# Mother_board1.net
KiCad netlist of a schematic drawn in Altium Designer
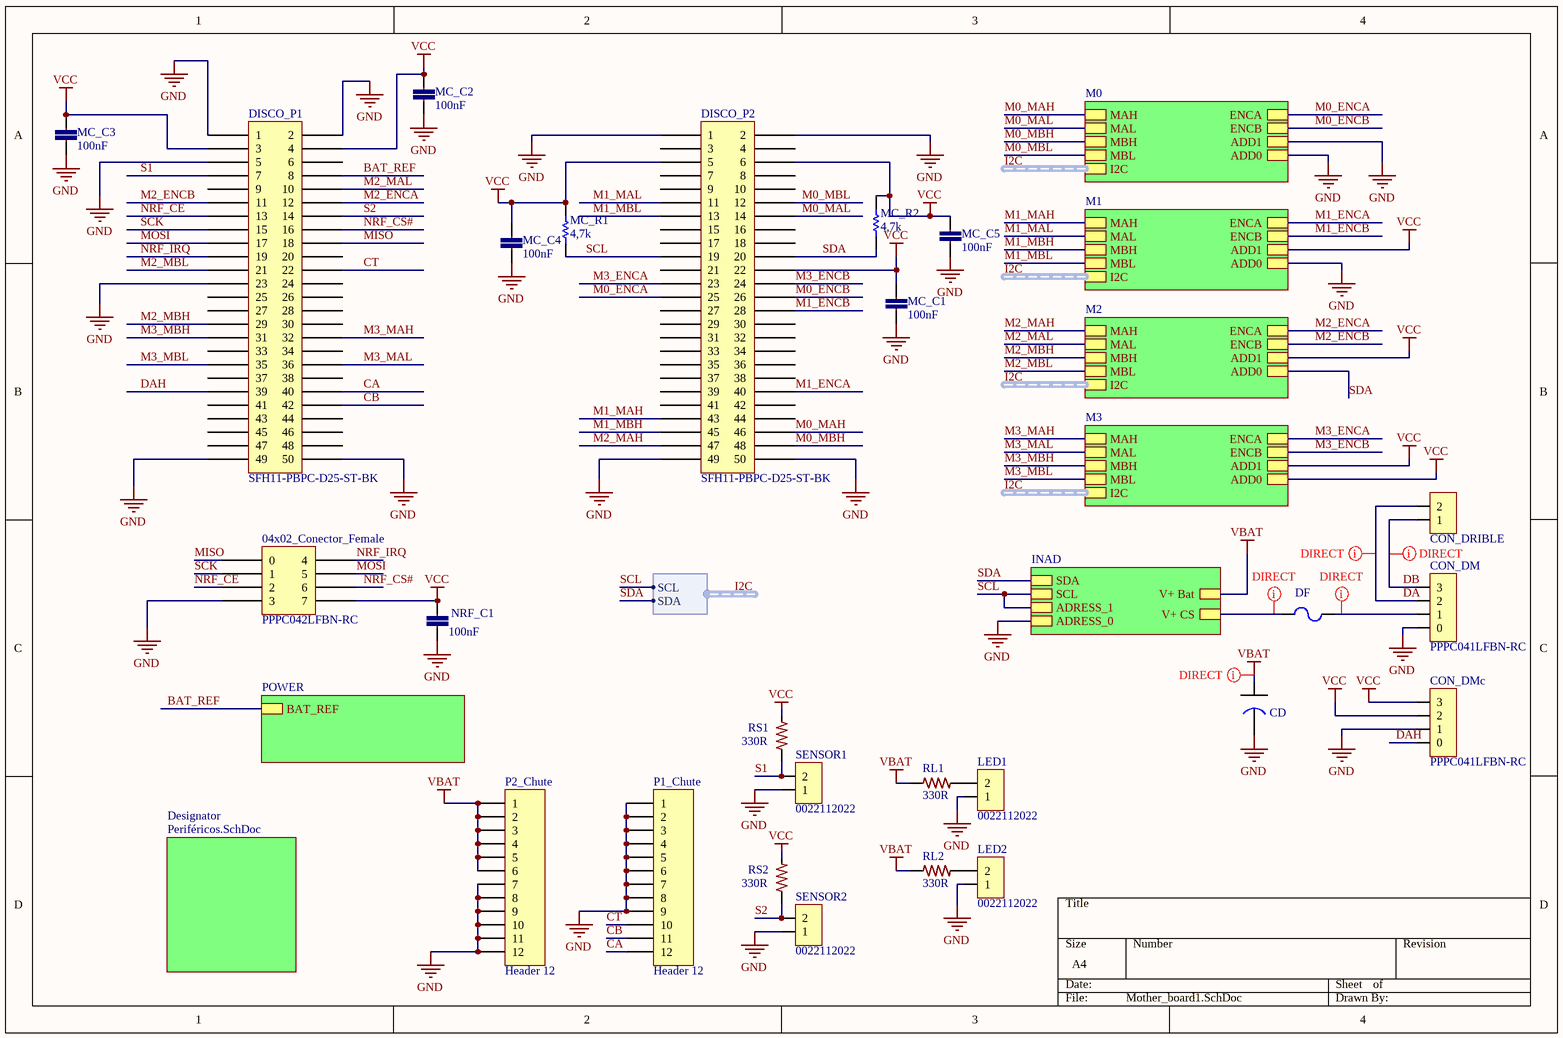
[diagram p0: Mother_board1.SchDoc]

(export (version "E")
  (design (tool "Eeschema 10.0.6"))
  (components
    (comp (ref "04x02_Conector_Female")
      (value "PPPC042LFBN-RC")
      (footprint "04x02_Conector_Female")
      (description "8 Position Header Connector 0.100\" (2.54mm) Through Hole Gold")
      (libsource (lib "Schlib1") (part "04x02_Conector_Female"))
    )
    (comp (ref "CD")
      (value "EEE-FK1C681GP")
      (footprint "EEE-FK1C681GP")
      (description "Aluminum Electrolytic Capacitors - SMD Al Lytic Cap SMT FK Series 105C")
      (libsource (lib "Schlib1") (part "CAP AL 680UF/16V"))
    )
    (comp (ref "CON_DM")
      (value "PPPC041LFBN-RC")
      (footprint "04x01_Conector_Female - duplicate")
      (description "4 Position Header Connector 0.100\" (2.54mm) Through Hole Gold")
      (libsource (lib "Schlib1") (part "04x01_Conector_Female-SCH"))
    )
    (comp (ref "CON_DMc")
      (value "PPPC041LFBN-RC")
      (footprint "04x01_Conector_Female - duplicate")
      (description "4 Position Header Connector 0.100\" (2.54mm) Through Hole Gold")
      (libsource (lib "Schlib1") (part "04x01_Conector_Female-SCH"))
    )
    (comp (ref "CON_DRIBLE")
      (value "0022112022")
      (footprint "02x01_Conector_Male")
      (description "CONN HEADER 2POS .100 VERT GOLD")
      (libsource (lib "Schlib1") (part "02x01_Conector_Male"))
    )
    (comp (ref "DF")
      (value "MF-MSMF250/16X")
      (footprint "RESC4632X16N")
      (description "PTC RESETTABLE .30A 30V 1812")
      (libsource (lib "IMBEL") (part "MF-MSMF250/16X-01.A.1"))
    )
    (comp (ref "DISCO_P1")
      (value "SFH11-PBPC-D25-ST-BK")
      (footprint "25x02_Conector_Female")
      (description "50 Position Header Connector 0.100\" (2.54mm) Through Hole Gold")
      (libsource (lib "Schlib1") (part "25x02_Conector_Female"))
    )
    (comp (ref "DISCO_P2")
      (value "SFH11-PBPC-D25-ST-BK")
      (footprint "25x02_Conector_Female")
      (description "50 Position Header Connector 0.100\" (2.54mm) Through Hole Gold")
      (libsource (lib "Schlib1") (part "25x02_Conector_Female"))
    )
    (comp (ref "LED1")
      (value "0022112022")
      (footprint "02x01_Conector_Male")
      (description "CONN HEADER 2POS .100 VERT GOLD")
      (libsource (lib "Schlib1") (part "02x01_Conector_Male"))
    )
    (comp (ref "LED2")
      (value "0022112022")
      (footprint "02x01_Conector_Male")
      (description "CONN HEADER 2POS .100 VERT GOLD")
      (libsource (lib "Schlib1") (part "02x01_Conector_Male"))
    )
    (comp (ref "MC_C1")
      (value "100nF")
      (footprint "0402-CAP")
      (description "CAP CER 0.1UF 10V 20% X5R 0402")
      (fields (field (name "PART NO") "VJ0402V104ZXQPBC"))
      (libsource (lib "IMBEL") (part "CC0402-100nF-A.12"))
    )
    (comp (ref "MC_C2")
      (value "100nF")
      (footprint "0402-CAP")
      (description "CAP CER 0.1UF 10V 20% X5R 0402")
      (fields (field (name "PART NO") "VJ0402V104ZXQPBC"))
      (libsource (lib "IMBEL") (part "CC0402-100nF-A.12"))
    )
    (comp (ref "MC_C3")
      (value "100nF")
      (footprint "0402-CAP")
      (description "CAP CER 0.1UF 10V 20% X5R 0402")
      (fields (field (name "PART NO") "VJ0402V104ZXQPBC"))
      (libsource (lib "") (part "CC0402-100nF-A.12_1"))
    )
    (comp (ref "MC_C4")
      (value "100nF")
      (footprint "0402-CAP")
      (description "CAP CER 0.1UF 10V 20% X5R 0402")
      (fields (field (name "PART NO") "VJ0402V104ZXQPBC"))
      (libsource (lib "IMBEL") (part "CC0402-100nF-A.12"))
    )
    (comp (ref "MC_C5")
      (value "100nF")
      (footprint "0402-CAP")
      (description "CAP CER 0.1UF 10V 20% X5R 0402")
      (fields (field (name "PART NO") "VJ0402V104ZXQPBC"))
      (libsource (lib "IMBEL") (part "CC0402-100nF-A.12"))
    )
    (comp (ref "MC_R1")
      (value "4,7k")
      (footprint "0402")
      (description "Resistor")
      (fields (field (name "PUBLISHER") "Altium Limited"))
      (libsource (lib "Miscellaneous Devices") (part "Res1"))
    )
    (comp (ref "MC_R2")
      (value "4,7k")
      (footprint "0402")
      (description "Resistor")
      (fields (field (name "PUBLISHER") "Altium Limited"))
      (libsource (lib "Miscellaneous Devices") (part "Res1"))
    )
    (comp (ref "NRF_C1")
      (value "100nF")
      (footprint "0402-CAP")
      (description "CAP CER 0.1UF 10V 20% X5R 0402")
      (fields (field (name "PART NO") "VJ0402V104ZXQPBC"))
      (libsource (lib "") (part "CC0402-100nF-A.12_1"))
    )
    (comp (ref "P1_Chute")
      (value "Header 12")
      (footprint "HDR1X12")
      (description "Header, 12-Pin")
      (fields (field (name "PUBLISHER") "Altium Limited"))
      (libsource (lib "Miscellaneous Connectors") (part "Header 12"))
    )
    (comp (ref "P2_Chute")
      (value "Header 12")
      (footprint "HDR1X12")
      (description "Header, 12-Pin")
      (fields (field (name "PUBLISHER") "Altium Limited"))
      (libsource (lib "Miscellaneous Connectors") (part "Header 12"))
    )
    (comp (ref "RL1")
      (value "330R")
      (footprint "0402-RES-HD")
      (description "RES 330 OHM 1/10W 1% 0402 SMD")
      (fields (field (name "PART NO") "ERJ-2RKF3300X"))
      (libsource (lib "IMBEL") (part "RESISTOR"))
    )
    (comp (ref "RL2")
      (value "330R")
      (footprint "0402-RES-HD")
      (description "RES 330 OHM 1/10W 1% 0402 SMD")
      (fields (field (name "PART NO") "ERJ-2RKF3300X"))
      (libsource (lib "IMBEL") (part "RESISTOR"))
    )
    (comp (ref "RS1")
      (value "330R")
      (footprint "0402-RES-HD")
      (description "RES 330 OHM 1/10W 1% 0402 SMD")
      (fields (field (name "PART NO") "ERJ-2RKF3300X"))
      (libsource (lib "IMBEL") (part "RESISTOR"))
    )
    (comp (ref "RS2")
      (value "330R")
      (footprint "0402-RES-HD")
      (description "RES 330 OHM 1/10W 1% 0402 SMD")
      (fields (field (name "PART NO") "ERJ-2RKF3300X"))
      (libsource (lib "IMBEL") (part "RESISTOR"))
    )
    (comp (ref "SENSOR1")
      (value "0022112022")
      (footprint "02x01_Conector_Male")
      (description "CONN HEADER 2POS .100 VERT GOLD")
      (libsource (lib "Schlib1") (part "02x01_Conector_Male"))
    )
    (comp (ref "SENSOR2")
      (value "0022112022")
      (footprint "02x01_Conector_Male")
      (description "CONN HEADER 2POS .100 VERT GOLD")
      (libsource (lib "Schlib1") (part "02x01_Conector_Male"))
    )
  )
  (nets
    (net (code "3") (name "/BAT_REF") (class "Default")
      (node (ref "DISCO_P1") (pin "8") (pinfunction "8_8") (pintype "passive"))
    )
    (net (code "4") (name "/CA") (class "Default")
      (node (ref "DISCO_P1") (pin "40") (pinfunction "40_40") (pintype "passive"))
      (node (ref "P1_Chute") (pin "12") (pinfunction "12_12") (pintype "passive"))
    )
    (net (code "5") (name "/CB") (class "Default")
      (node (ref "DISCO_P1") (pin "42") (pinfunction "42_42") (pintype "passive"))
      (node (ref "P1_Chute") (pin "11") (pinfunction "11_11") (pintype "passive"))
    )
    (net (code "6") (name "/CT") (class "Default")
      (node (ref "DISCO_P1") (pin "22") (pinfunction "22_22") (pintype "passive"))
      (node (ref "P1_Chute") (pin "10") (pinfunction "10_10") (pintype "passive"))
    )
    (net (code "7") (name "/DA") (class "Default")
      (node (ref "CON_DM") (pin "2") (pinfunction "2_2") (pintype "passive"))
      (node (ref "CON_DRIBLE") (pin "2") (pinfunction "2_2") (pintype "passive"))
    )
    (net (code "8") (name "/DAH") (class "Default")
      (node (ref "CON_DMc") (pin "0") (pinfunction "0_0") (pintype "passive"))
      (node (ref "DISCO_P1") (pin "39") (pinfunction "39_39") (pintype "passive"))
    )
    (net (code "9") (name "/DB") (class "Default")
      (node (ref "CON_DM") (pin "3") (pinfunction "3_3") (pintype "passive"))
      (node (ref "CON_DRIBLE") (pin "1") (pinfunction "1_1") (pintype "passive"))
    )
    (net (code "11") (name "/M0_ENCA") (class "Default")
      (node (ref "DISCO_P2") (pin "25") (pinfunction "25_25") (pintype "passive"))
    )
    (net (code "12") (name "/M0_ENCB") (class "Default")
      (node (ref "DISCO_P2") (pin "26") (pinfunction "26_26") (pintype "passive"))
    )
    (net (code "13") (name "/M0_MAH") (class "Default")
      (node (ref "DISCO_P2") (pin "46") (pinfunction "46_46") (pintype "passive"))
    )
    (net (code "14") (name "/M0_MAL") (class "Default")
      (node (ref "DISCO_P2") (pin "14") (pinfunction "14_14") (pintype "passive"))
    )
    (net (code "15") (name "/M0_MBH") (class "Default")
      (node (ref "DISCO_P2") (pin "48") (pinfunction "48_48") (pintype "passive"))
    )
    (net (code "16") (name "/M0_MBL") (class "Default")
      (node (ref "DISCO_P2") (pin "12") (pinfunction "12_12") (pintype "passive"))
    )
    (net (code "17") (name "/M1_ENCA") (class "Default")
      (node (ref "DISCO_P2") (pin "40") (pinfunction "40_40") (pintype "passive"))
    )
    (net (code "18") (name "/M1_ENCB") (class "Default")
      (node (ref "DISCO_P2") (pin "28") (pinfunction "28_28") (pintype "passive"))
    )
    (net (code "19") (name "/M1_MAH") (class "Default")
      (node (ref "DISCO_P2") (pin "43") (pinfunction "43_43") (pintype "passive"))
    )
    (net (code "20") (name "/M1_MAL") (class "Default")
      (node (ref "DISCO_P2") (pin "11") (pinfunction "11_11") (pintype "passive"))
    )
    (net (code "21") (name "/M1_MBH") (class "Default")
      (node (ref "DISCO_P2") (pin "45") (pinfunction "45_45") (pintype "passive"))
    )
    (net (code "22") (name "/M1_MBL") (class "Default")
      (node (ref "DISCO_P2") (pin "13") (pinfunction "13_13") (pintype "passive"))
    )
    (net (code "23") (name "/M2_ENCA") (class "Default")
      (node (ref "DISCO_P1") (pin "12") (pinfunction "12_12") (pintype "passive"))
    )
    (net (code "24") (name "/M2_ENCB") (class "Default")
      (node (ref "DISCO_P1") (pin "11") (pinfunction "11_11") (pintype "passive"))
    )
    (net (code "25") (name "/M2_MAH") (class "Default")
      (node (ref "DISCO_P2") (pin "47") (pinfunction "47_47") (pintype "passive"))
    )
    (net (code "26") (name "/M2_MAL") (class "Default")
      (node (ref "DISCO_P1") (pin "10") (pinfunction "10_10") (pintype "passive"))
    )
    (net (code "27") (name "/M2_MBH") (class "Default")
      (node (ref "DISCO_P1") (pin "29") (pinfunction "29_29") (pintype "passive"))
    )
    (net (code "28") (name "/M2_MBL") (class "Default")
      (node (ref "DISCO_P1") (pin "21") (pinfunction "21_21") (pintype "passive"))
    )
    (net (code "29") (name "/M3_ENCA") (class "Default")
      (node (ref "DISCO_P2") (pin "23") (pinfunction "23_23") (pintype "passive"))
    )
    (net (code "30") (name "/M3_ENCB") (class "Default")
      (node (ref "DISCO_P2") (pin "24") (pinfunction "24_24") (pintype "passive"))
    )
    (net (code "31") (name "/M3_MAH") (class "Default")
      (node (ref "DISCO_P1") (pin "32") (pinfunction "32_32") (pintype "passive"))
    )
    (net (code "32") (name "/M3_MAL") (class "Default")
      (node (ref "DISCO_P1") (pin "36") (pinfunction "36_36") (pintype "passive"))
    )
    (net (code "33") (name "/M3_MBH") (class "Default")
      (node (ref "DISCO_P1") (pin "31") (pinfunction "31_31") (pintype "passive"))
    )
    (net (code "34") (name "/M3_MBL") (class "Default")
      (node (ref "DISCO_P1") (pin "35") (pinfunction "35_35") (pintype "passive"))
    )
    (net (code "35") (name "/MISO") (class "Default")
      (node (ref "04x02_Conector_Female") (pin "0") (pinfunction "0_0") (pintype "passive"))
      (node (ref "DISCO_P1") (pin "18") (pinfunction "18_18") (pintype "passive"))
    )
    (net (code "36") (name "/MOSI") (class "Default")
      (node (ref "04x02_Conector_Female") (pin "5") (pinfunction "5_5") (pintype "passive"))
      (node (ref "DISCO_P1") (pin "17") (pinfunction "17_17") (pintype "passive"))
    )
    (net (code "37") (name "/NRF_CE") (class "Default")
      (node (ref "04x02_Conector_Female") (pin "2") (pinfunction "2_2") (pintype "passive"))
      (node (ref "DISCO_P1") (pin "13") (pinfunction "13_13") (pintype "passive"))
    )
    (net (code "38") (name "/NRF_CS#") (class "Default")
      (node (ref "04x02_Conector_Female") (pin "6") (pinfunction "6_6") (pintype "passive"))
      (node (ref "DISCO_P1") (pin "16") (pinfunction "16_16") (pintype "passive"))
    )
    (net (code "39") (name "/NRF_IRQ") (class "Default")
      (node (ref "04x02_Conector_Female") (pin "4") (pinfunction "4_4") (pintype "passive"))
      (node (ref "DISCO_P1") (pin "19") (pinfunction "19_19") (pintype "passive"))
    )
    (net (code "40") (name "/S1") (class "Default")
      (node (ref "DISCO_P1") (pin "7") (pinfunction "7_7") (pintype "passive"))
      (node (ref "RS1") (pin "1") (pinfunction "1_1") (pintype "passive"))
      (node (ref "SENSOR1") (pin "2") (pinfunction "2_2") (pintype "passive"))
    )
    (net (code "41") (name "/S2") (class "Default")
      (node (ref "DISCO_P1") (pin "14") (pinfunction "14_14") (pintype "passive"))
      (node (ref "RS2") (pin "1") (pinfunction "1_1") (pintype "passive"))
      (node (ref "SENSOR2") (pin "2") (pinfunction "2_2") (pintype "passive"))
    )
    (net (code "42") (name "/SCK") (class "Default")
      (node (ref "04x02_Conector_Female") (pin "1") (pinfunction "1_1") (pintype "passive"))
      (node (ref "DISCO_P1") (pin "15") (pinfunction "15_15") (pintype "passive"))
    )
    (net (code "43") (name "/SCL") (class "Default")
      (node (ref "DISCO_P2") (pin "19") (pinfunction "19_19") (pintype "passive"))
      (node (ref "MC_R1") (pin "1") (pinfunction "1_1") (pintype "passive"))
    )
    (net (code "44") (name "/SDA") (class "Default")
      (node (ref "DISCO_P2") (pin "20") (pinfunction "20_20") (pintype "passive"))
      (node (ref "MC_R2") (pin "1") (pinfunction "1_1") (pintype "passive"))
    )
    (net (code "45") (name "/V+ CS") (class "Default")
      (node (ref "DF") (pin "2") (pinfunction "2_2") (pintype "passive"))
    )
    (net (code "47") (name "GND") (class "Default")
      (node (ref "04x02_Conector_Female") (pin "3") (pinfunction "3_3") (pintype "passive"))
      (node (ref "CD") (pin "2") (pinfunction "2_2") (pintype "passive"))
      (node (ref "CON_DM") (pin "0") (pinfunction "0_0") (pintype "passive"))
      (node (ref "CON_DMc") (pin "1") (pinfunction "1_1") (pintype "passive"))
      (node (ref "DISCO_P1") (pin "1") (pinfunction "1_1") (pintype "passive"))
      (node (ref "DISCO_P1") (pin "2") (pinfunction "2_2") (pintype "passive"))
      (node (ref "DISCO_P1") (pin "23") (pinfunction "23_23") (pintype "passive"))
      (node (ref "DISCO_P1") (pin "49") (pinfunction "49_49") (pintype "passive"))
      (node (ref "DISCO_P1") (pin "5") (pinfunction "5_5") (pintype "passive"))
      (node (ref "DISCO_P1") (pin "50") (pinfunction "50_50") (pintype "passive"))
      (node (ref "DISCO_P2") (pin "1") (pinfunction "1_1") (pintype "passive"))
      (node (ref "DISCO_P2") (pin "2") (pinfunction "2_2") (pintype "passive"))
      (node (ref "DISCO_P2") (pin "49") (pinfunction "49_49") (pintype "passive"))
      (node (ref "DISCO_P2") (pin "50") (pinfunction "50_50") (pintype "passive"))
      (node (ref "LED1") (pin "1") (pinfunction "1_1") (pintype "passive"))
      (node (ref "LED2") (pin "1") (pinfunction "1_1") (pintype "passive"))
      (node (ref "MC_C1") (pin "1") (pinfunction "1_1") (pintype "passive"))
      (node (ref "MC_C2") (pin "1") (pinfunction "1_1") (pintype "passive"))
      (node (ref "MC_C3") (pin "2") (pinfunction "2_2") (pintype "passive"))
      (node (ref "MC_C4") (pin "1") (pinfunction "1_1") (pintype "passive"))
      (node (ref "MC_C5") (pin "1") (pinfunction "1_1") (pintype "passive"))
      (node (ref "NRF_C1") (pin "2") (pinfunction "2_2") (pintype "passive"))
      (node (ref "P1_Chute") (pin "1") (pinfunction "1_1") (pintype "passive"))
      (node (ref "P1_Chute") (pin "2") (pinfunction "2_2") (pintype "passive"))
      (node (ref "P1_Chute") (pin "3") (pinfunction "3_3") (pintype "passive"))
      (node (ref "P1_Chute") (pin "4") (pinfunction "4_4") (pintype "passive"))
      (node (ref "P1_Chute") (pin "5") (pinfunction "5_5") (pintype "passive"))
      (node (ref "P1_Chute") (pin "6") (pinfunction "6_6") (pintype "passive"))
      (node (ref "P1_Chute") (pin "7") (pinfunction "7_7") (pintype "passive"))
      (node (ref "P1_Chute") (pin "8") (pinfunction "8_8") (pintype "passive"))
      (node (ref "P1_Chute") (pin "9") (pinfunction "9_9") (pintype "passive"))
      (node (ref "P2_Chute") (pin "10") (pinfunction "10_10") (pintype "passive"))
      (node (ref "P2_Chute") (pin "11") (pinfunction "11_11") (pintype "passive"))
      (node (ref "P2_Chute") (pin "12") (pinfunction "12_12") (pintype "passive"))
      (node (ref "P2_Chute") (pin "7") (pinfunction "7_7") (pintype "passive"))
      (node (ref "P2_Chute") (pin "8") (pinfunction "8_8") (pintype "passive"))
      (node (ref "P2_Chute") (pin "9") (pinfunction "9_9") (pintype "passive"))
      (node (ref "SENSOR1") (pin "1") (pinfunction "1_1") (pintype "passive"))
      (node (ref "SENSOR2") (pin "1") (pinfunction "1_1") (pintype "passive"))
    )
    (net (code "48") (name "Net-(CON_DM-Pad1)") (class "Default")
      (node (ref "CON_DM") (pin "1") (pinfunction "1_1") (pintype "passive"))
      (node (ref "DF") (pin "1") (pinfunction "1_1") (pintype "passive"))
    )
    (net (code "49") (name "Net-(LED1-Pad2)") (class "Default")
      (node (ref "LED1") (pin "2") (pinfunction "2_2") (pintype "passive"))
      (node (ref "RL1") (pin "2") (pinfunction "2_2") (pintype "passive"))
    )
    (net (code "50") (name "Net-(LED2-Pad2)") (class "Default")
      (node (ref "LED2") (pin "2") (pinfunction "2_2") (pintype "passive"))
      (node (ref "RL2") (pin "2") (pinfunction "2_2") (pintype "passive"))
    )
    (net (code "51") (name "VBAT") (class "Default")
      (node (ref "CD") (pin "1") (pinfunction "1_1") (pintype "passive"))
      (node (ref "P2_Chute") (pin "1") (pinfunction "1_1") (pintype "passive"))
      (node (ref "P2_Chute") (pin "2") (pinfunction "2_2") (pintype "passive"))
      (node (ref "P2_Chute") (pin "3") (pinfunction "3_3") (pintype "passive"))
      (node (ref "P2_Chute") (pin "4") (pinfunction "4_4") (pintype "passive"))
      (node (ref "P2_Chute") (pin "5") (pinfunction "5_5") (pintype "passive"))
      (node (ref "P2_Chute") (pin "6") (pinfunction "6_6") (pintype "passive"))
      (node (ref "RL1") (pin "1") (pinfunction "1_1") (pintype "passive"))
      (node (ref "RL2") (pin "1") (pinfunction "1_1") (pintype "passive"))
    )
    (net (code "52") (name "VCC") (class "Default")
      (node (ref "04x02_Conector_Female") (pin "7") (pinfunction "7_7") (pintype "passive"))
      (node (ref "CON_DMc") (pin "2") (pinfunction "2_2") (pintype "passive"))
      (node (ref "CON_DMc") (pin "3") (pinfunction "3_3") (pintype "passive"))
      (node (ref "DISCO_P1") (pin "3") (pinfunction "3_3") (pintype "passive"))
      (node (ref "DISCO_P1") (pin "4") (pinfunction "4_4") (pintype "passive"))
      (node (ref "DISCO_P2") (pin "22") (pinfunction "22_22") (pintype "passive"))
      (node (ref "DISCO_P2") (pin "5") (pinfunction "5_5") (pintype "passive"))
      (node (ref "DISCO_P2") (pin "6") (pinfunction "6_6") (pintype "passive"))
      (node (ref "MC_C1") (pin "2") (pinfunction "2_2") (pintype "passive"))
      (node (ref "MC_C2") (pin "2") (pinfunction "2_2") (pintype "passive"))
      (node (ref "MC_C3") (pin "1") (pinfunction "1_1") (pintype "passive"))
      (node (ref "MC_C4") (pin "2") (pinfunction "2_2") (pintype "passive"))
      (node (ref "MC_C5") (pin "2") (pinfunction "2_2") (pintype "passive"))
      (node (ref "MC_R1") (pin "2") (pinfunction "2_2") (pintype "passive"))
      (node (ref "MC_R2") (pin "2") (pinfunction "2_2") (pintype "passive"))
      (node (ref "NRF_C1") (pin "1") (pinfunction "1_1") (pintype "passive"))
      (node (ref "RS1") (pin "2") (pinfunction "2_2") (pintype "passive"))
      (node (ref "RS2") (pin "2") (pinfunction "2_2") (pintype "passive"))
    )
    (net (code "53") (name "unconnected-(DISCO_P1-Pad6)") (class "Default")
      (node (ref "DISCO_P1") (pin "6") (pinfunction "6_6") (pintype "passive"))
    )
    (net (code "54") (name "unconnected-(DISCO_P1-Pad9)") (class "Default")
      (node (ref "DISCO_P1") (pin "9") (pinfunction "9_9") (pintype "passive"))
    )
    (net (code "55") (name "unconnected-(DISCO_P1-Pad20)") (class "Default")
      (node (ref "DISCO_P1") (pin "20") (pinfunction "20_20") (pintype "passive"))
    )
    (net (code "56") (name "unconnected-(DISCO_P1-Pad24)") (class "Default")
      (node (ref "DISCO_P1") (pin "24") (pinfunction "24_24") (pintype "passive"))
    )
    (net (code "57") (name "unconnected-(DISCO_P1-Pad25)") (class "Default")
      (node (ref "DISCO_P1") (pin "25") (pinfunction "25_25") (pintype "passive"))
    )
    (net (code "58") (name "unconnected-(DISCO_P1-Pad26)") (class "Default")
      (node (ref "DISCO_P1") (pin "26") (pinfunction "26_26") (pintype "passive"))
    )
    (net (code "59") (name "unconnected-(DISCO_P1-Pad27)") (class "Default")
      (node (ref "DISCO_P1") (pin "27") (pinfunction "27_27") (pintype "passive"))
    )
    (net (code "60") (name "unconnected-(DISCO_P1-Pad28)") (class "Default")
      (node (ref "DISCO_P1") (pin "28") (pinfunction "28_28") (pintype "passive"))
    )
    (net (code "61") (name "unconnected-(DISCO_P1-Pad30)") (class "Default")
      (node (ref "DISCO_P1") (pin "30") (pinfunction "30_30") (pintype "passive"))
    )
    (net (code "62") (name "unconnected-(DISCO_P1-Pad33)") (class "Default")
      (node (ref "DISCO_P1") (pin "33") (pinfunction "33_33") (pintype "passive"))
    )
    (net (code "63") (name "unconnected-(DISCO_P1-Pad34)") (class "Default")
      (node (ref "DISCO_P1") (pin "34") (pinfunction "34_34") (pintype "passive"))
    )
    (net (code "64") (name "unconnected-(DISCO_P1-Pad37)") (class "Default")
      (node (ref "DISCO_P1") (pin "37") (pinfunction "37_37") (pintype "passive"))
    )
    (net (code "65") (name "unconnected-(DISCO_P1-Pad38)") (class "Default")
      (node (ref "DISCO_P1") (pin "38") (pinfunction "38_38") (pintype "passive"))
    )
    (net (code "66") (name "unconnected-(DISCO_P1-Pad41)") (class "Default")
      (node (ref "DISCO_P1") (pin "41") (pinfunction "41_41") (pintype "passive"))
    )
    (net (code "67") (name "unconnected-(DISCO_P1-Pad43)") (class "Default")
      (node (ref "DISCO_P1") (pin "43") (pinfunction "43_43") (pintype "passive"))
    )
    (net (code "68") (name "unconnected-(DISCO_P1-Pad44)") (class "Default")
      (node (ref "DISCO_P1") (pin "44") (pinfunction "44_44") (pintype "passive"))
    )
    (net (code "69") (name "unconnected-(DISCO_P1-Pad45)") (class "Default")
      (node (ref "DISCO_P1") (pin "45") (pinfunction "45_45") (pintype "passive"))
    )
    (net (code "70") (name "unconnected-(DISCO_P1-Pad46)") (class "Default")
      (node (ref "DISCO_P1") (pin "46") (pinfunction "46_46") (pintype "passive"))
    )
    (net (code "71") (name "unconnected-(DISCO_P1-Pad47)") (class "Default")
      (node (ref "DISCO_P1") (pin "47") (pinfunction "47_47") (pintype "passive"))
    )
    (net (code "72") (name "unconnected-(DISCO_P1-Pad48)") (class "Default")
      (node (ref "DISCO_P1") (pin "48") (pinfunction "48_48") (pintype "passive"))
    )
    (net (code "73") (name "unconnected-(DISCO_P2-Pad3)") (class "Default")
      (node (ref "DISCO_P2") (pin "3") (pinfunction "3_3") (pintype "passive"))
    )
    (net (code "74") (name "unconnected-(DISCO_P2-Pad4)") (class "Default")
      (node (ref "DISCO_P2") (pin "4") (pinfunction "4_4") (pintype "passive"))
    )
    (net (code "75") (name "unconnected-(DISCO_P2-Pad7)") (class "Default")
      (node (ref "DISCO_P2") (pin "7") (pinfunction "7_7") (pintype "passive"))
    )
    (net (code "76") (name "unconnected-(DISCO_P2-Pad8)") (class "Default")
      (node (ref "DISCO_P2") (pin "8") (pinfunction "8_8") (pintype "passive"))
    )
    (net (code "77") (name "unconnected-(DISCO_P2-Pad9)") (class "Default")
      (node (ref "DISCO_P2") (pin "9") (pinfunction "9_9") (pintype "passive"))
    )
    (net (code "78") (name "unconnected-(DISCO_P2-Pad10)") (class "Default")
      (node (ref "DISCO_P2") (pin "10") (pinfunction "10_10") (pintype "passive"))
    )
    (net (code "79") (name "unconnected-(DISCO_P2-Pad15)") (class "Default")
      (node (ref "DISCO_P2") (pin "15") (pinfunction "15_15") (pintype "passive"))
    )
    (net (code "80") (name "unconnected-(DISCO_P2-Pad16)") (class "Default")
      (node (ref "DISCO_P2") (pin "16") (pinfunction "16_16") (pintype "passive"))
    )
    (net (code "81") (name "unconnected-(DISCO_P2-Pad17)") (class "Default")
      (node (ref "DISCO_P2") (pin "17") (pinfunction "17_17") (pintype "passive"))
    )
    (net (code "82") (name "unconnected-(DISCO_P2-Pad18)") (class "Default")
      (node (ref "DISCO_P2") (pin "18") (pinfunction "18_18") (pintype "passive"))
    )
    (net (code "83") (name "unconnected-(DISCO_P2-Pad21)") (class "Default")
      (node (ref "DISCO_P2") (pin "21") (pinfunction "21_21") (pintype "passive"))
    )
    (net (code "84") (name "unconnected-(DISCO_P2-Pad27)") (class "Default")
      (node (ref "DISCO_P2") (pin "27") (pinfunction "27_27") (pintype "passive"))
    )
    (net (code "85") (name "unconnected-(DISCO_P2-Pad29)") (class "Default")
      (node (ref "DISCO_P2") (pin "29") (pinfunction "29_29") (pintype "passive"))
    )
    (net (code "86") (name "unconnected-(DISCO_P2-Pad30)") (class "Default")
      (node (ref "DISCO_P2") (pin "30") (pinfunction "30_30") (pintype "passive"))
    )
    (net (code "87") (name "unconnected-(DISCO_P2-Pad31)") (class "Default")
      (node (ref "DISCO_P2") (pin "31") (pinfunction "31_31") (pintype "passive"))
    )
    (net (code "88") (name "unconnected-(DISCO_P2-Pad32)") (class "Default")
      (node (ref "DISCO_P2") (pin "32") (pinfunction "32_32") (pintype "passive"))
    )
    (net (code "89") (name "unconnected-(DISCO_P2-Pad33)") (class "Default")
      (node (ref "DISCO_P2") (pin "33") (pinfunction "33_33") (pintype "passive"))
    )
    (net (code "90") (name "unconnected-(DISCO_P2-Pad34)") (class "Default")
      (node (ref "DISCO_P2") (pin "34") (pinfunction "34_34") (pintype "passive"))
    )
    (net (code "91") (name "unconnected-(DISCO_P2-Pad35)") (class "Default")
      (node (ref "DISCO_P2") (pin "35") (pinfunction "35_35") (pintype "passive"))
    )
    (net (code "92") (name "unconnected-(DISCO_P2-Pad36)") (class "Default")
      (node (ref "DISCO_P2") (pin "36") (pinfunction "36_36") (pintype "passive"))
    )
    (net (code "93") (name "unconnected-(DISCO_P2-Pad37)") (class "Default")
      (node (ref "DISCO_P2") (pin "37") (pinfunction "37_37") (pintype "passive"))
    )
    (net (code "94") (name "unconnected-(DISCO_P2-Pad38)") (class "Default")
      (node (ref "DISCO_P2") (pin "38") (pinfunction "38_38") (pintype "passive"))
    )
    (net (code "95") (name "unconnected-(DISCO_P2-Pad39)") (class "Default")
      (node (ref "DISCO_P2") (pin "39") (pinfunction "39_39") (pintype "passive"))
    )
    (net (code "96") (name "unconnected-(DISCO_P2-Pad41)") (class "Default")
      (node (ref "DISCO_P2") (pin "41") (pinfunction "41_41") (pintype "passive"))
    )
    (net (code "97") (name "unconnected-(DISCO_P2-Pad42)") (class "Default")
      (node (ref "DISCO_P2") (pin "42") (pinfunction "42_42") (pintype "passive"))
    )
    (net (code "98") (name "unconnected-(DISCO_P2-Pad44)") (class "Default")
      (node (ref "DISCO_P2") (pin "44") (pinfunction "44_44") (pintype "passive"))
    )
  )
)
